# MOD-W_V03.net
KiCad netlist of a schematic drawn in EAGLE
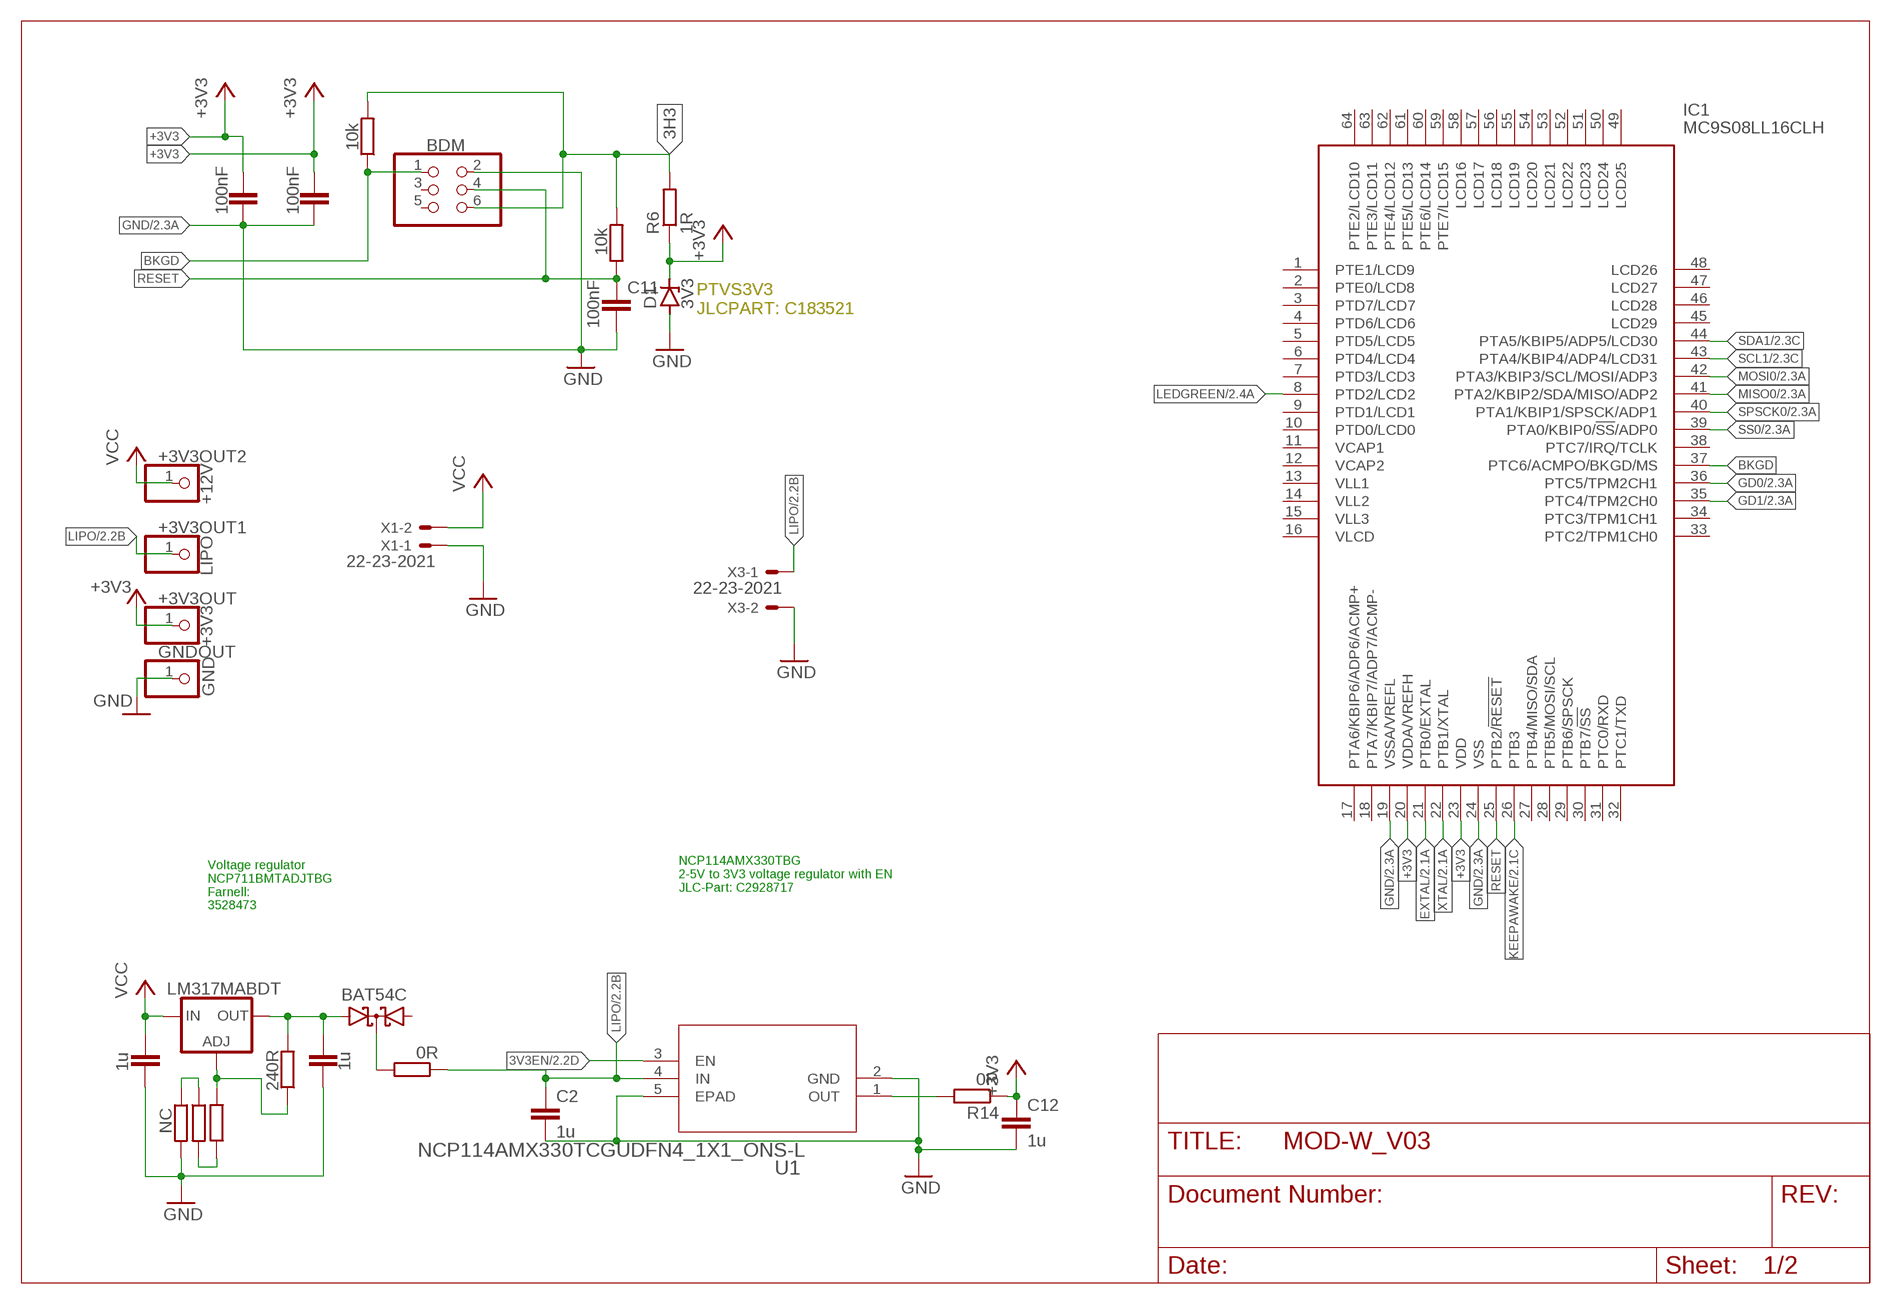
[diagram p0: schematic, sheet 1]
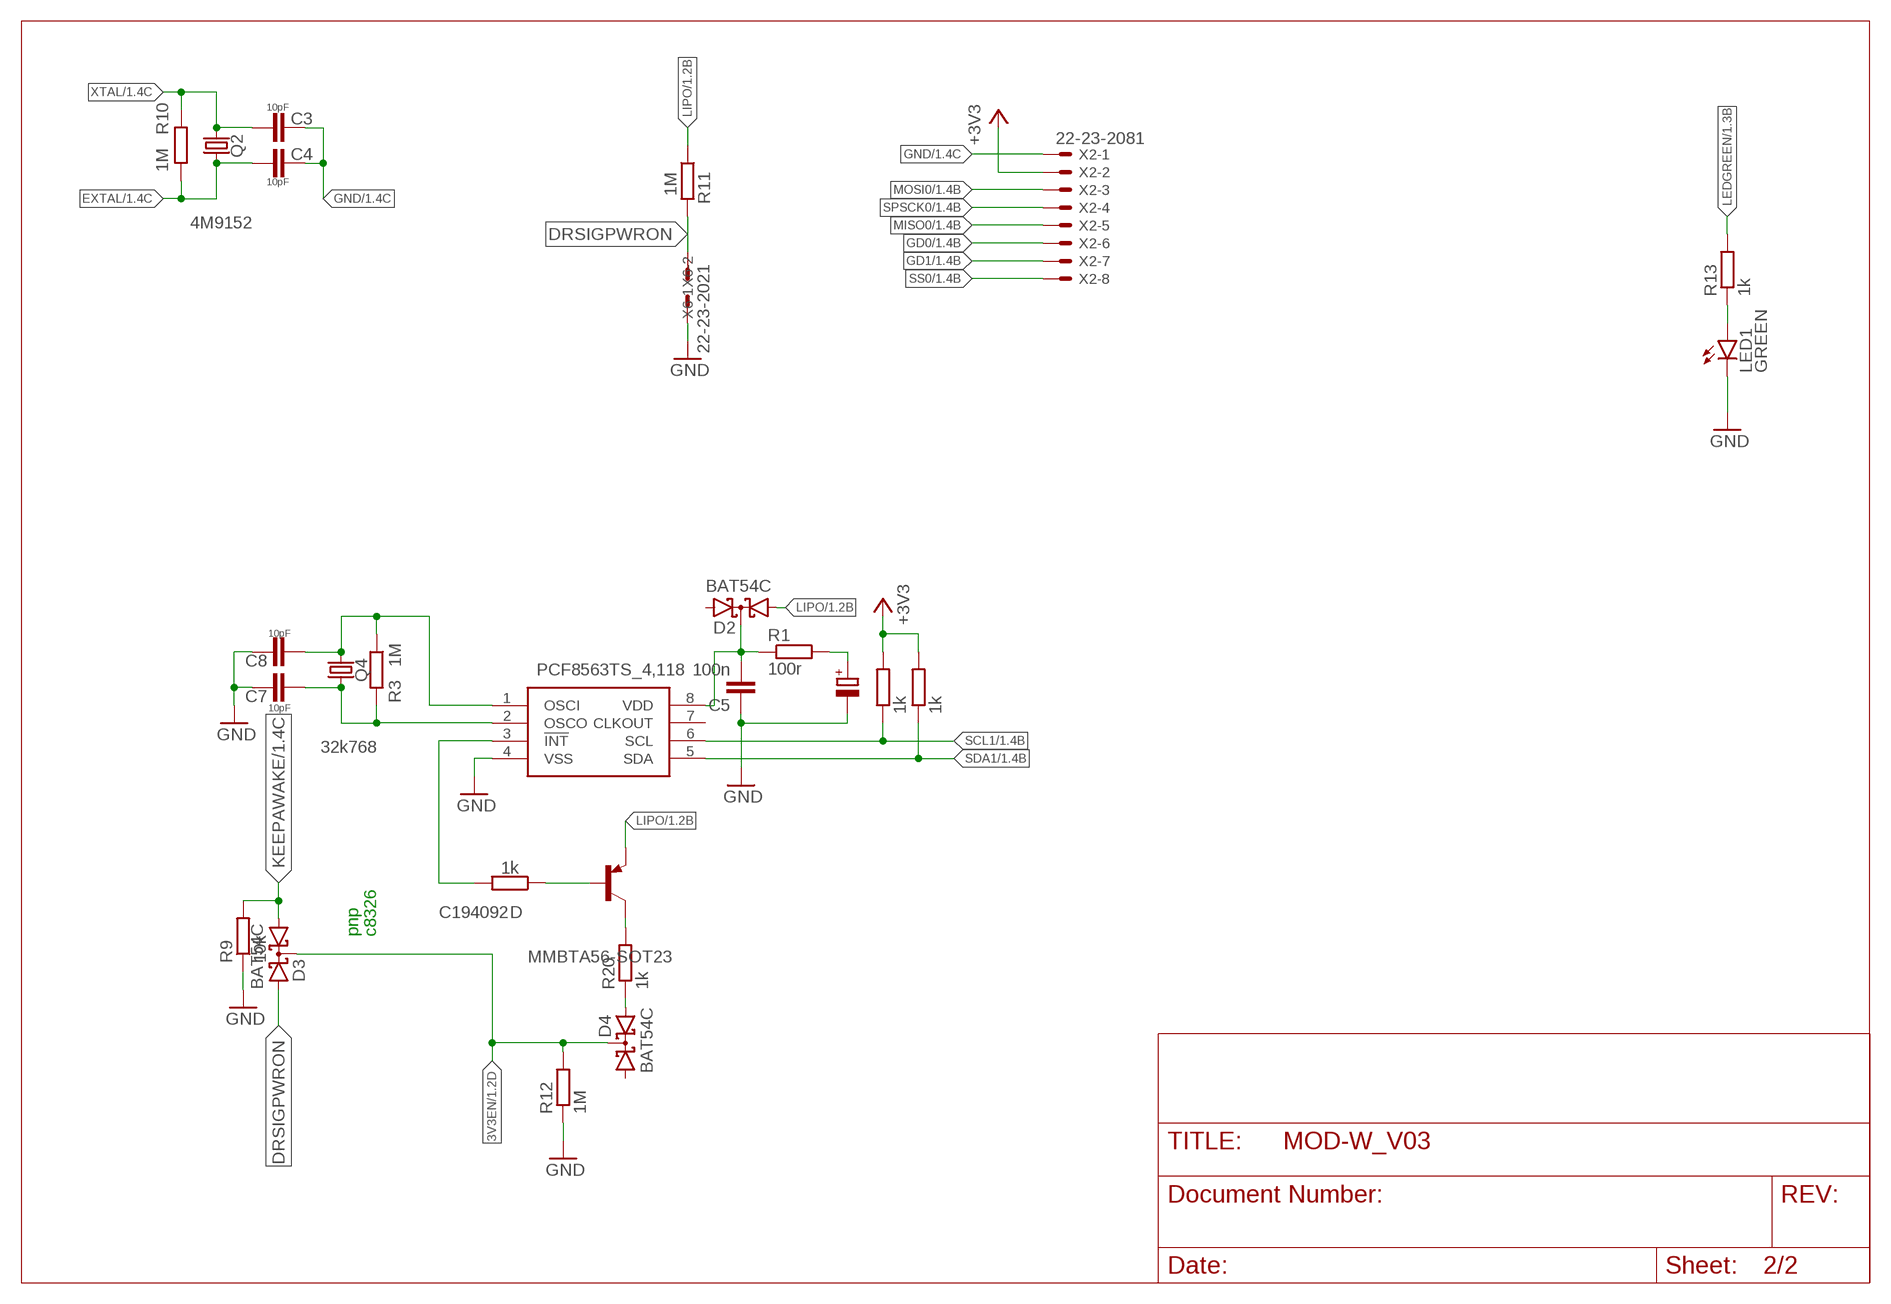
[diagram p1: schematic, sheet 2]

(export (version "E")
  (design (tool "Eeschema 10.0.6"))
  (components
    (comp (ref "+3V3OUT")
      (value "+3V3")
      (footprint "eagle-import:1X01")
      (libsource (lib "eagle-import") (part "PINHD-1X1"))
    )
    (comp (ref "+3V3OUT1")
      (value "LIPO")
      (footprint "eagle-import:1X01")
      (libsource (lib "eagle-import") (part "PINHD-1X1"))
    )
    (comp (ref "+3V3OUT2")
      (value "+12V")
      (footprint "eagle-import:1X01")
      (libsource (lib "eagle-import") (part "PINHD-1X1"))
    )
    (comp (ref "BDM")
      (value "PINHD-2X3")
      (footprint "eagle-import:2X03")
      (libsource (lib "eagle-import") (part "PINHD-2X3"))
    )
    (comp (ref "C1")
      (value "1u")
      (footprint "eagle-import:C0805")
      (libsource (lib "eagle-import") (part "C-EUC0805"))
    )
    (comp (ref "C2")
      (value "1u")
      (footprint "eagle-import:C0805")
      (libsource (lib "eagle-import") (part "C-EUC0805"))
    )
    (comp (ref "C9")
      (value "100nF")
      (footprint "eagle-import:C0805")
      (libsource (lib "eagle-import") (part "C-EUC0805"))
    )
    (comp (ref "C10")
      (value "100nF")
      (footprint "eagle-import:C0805")
      (libsource (lib "eagle-import") (part "C-EUC0805"))
    )
    (comp (ref "C11")
      (value "100nF")
      (footprint "eagle-import:C0805")
      (libsource (lib "eagle-import") (part "C-EUC0805"))
    )
    (comp (ref "C12")
      (value "1u")
      (footprint "eagle-import:C0805")
      (libsource (lib "eagle-import") (part "C-EUC0805"))
    )
    (comp (ref "C13")
      (value "1u")
      (footprint "eagle-import:C0805")
      (libsource (lib "eagle-import") (part "C-EUC0805"))
    )
    (comp (ref "D1")
      (value "3V3")
      (footprint "eagle-import:SOD80C")
      (libsource (lib "eagle-import") (part "ZENER-DIODESOD80C"))
    )
    (comp (ref "D7")
      (value "BAT54C")
      (footprint "eagle-import:SOT23")
      (libsource (lib "eagle-import") (part "BAT54C"))
    )
    (comp (ref "GNDOUT")
      (value "GND")
      (footprint "eagle-import:1X01")
      (libsource (lib "eagle-import") (part "PINHD-1X1"))
    )
    (comp (ref "IC1")
      (value "MC9S08LL16CLH")
      (footprint "eagle-import:QFP50P1200X1200X160-64N")
      (fields (field (name "MOUSER_PART_NUMBER") "841-MC9S08LL16CLH"))
      (libsource (lib "eagle-import") (part "MC9S08LL16CLH"))
    )
    (comp (ref "IC4")
      (value "LM317MABDT")
      (footprint "eagle-import:DPACK")
      (libsource (lib "eagle-import") (part "v-reg_409_LM317?MABDT"))
    )
    (comp (ref "R2")
      (value "NC")
      (footprint "eagle-import:R0805")
      (libsource (lib "eagle-import") (part "R-EU_R0805"))
    )
    (comp (ref "R6")
      (value "1R")
      (footprint "eagle-import:R0805")
      (libsource (lib "eagle-import") (part "R-EU_R0805"))
    )
    (comp (ref "R7")
      (value "0R")
      (footprint "eagle-import:R0805")
      (libsource (lib "eagle-import") (part "R-EU_R0805"))
    )
    (comp (ref "R14")
      (value "0R")
      (footprint "eagle-import:R0805")
      (libsource (lib "eagle-import") (part "R-EU_R0805"))
    )
    (comp (ref "R15")
      (value "240R")
      (footprint "eagle-import:R0805")
      (libsource (lib "eagle-import") (part "R-EU_R0805"))
    )
    (comp (ref "R16")
      (value "10k")
      (footprint "eagle-import:R0805")
      (libsource (lib "eagle-import") (part "R-EU_R0805"))
    )
    (comp (ref "R17")
      (value "10k")
      (footprint "eagle-import:R0805")
      (libsource (lib "eagle-import") (part "R-EU_R0805"))
    )
    (comp (ref "R18")
      (value "NC")
      (footprint "eagle-import:R0805")
      (libsource (lib "eagle-import") (part "R-EU_R0805"))
    )
    (comp (ref "R19")
      (value "NC")
      (footprint "eagle-import:R0805")
      (libsource (lib "eagle-import") (part "R-EU_R0805"))
    )
    (comp (ref "U1")
      (value "NCP114AMX330TCGUDFN4_1X1_ONS-L")
      (footprint "eagle-import:UDFN4_1X1_ONS-L")
      (fields
        (field (name "MANUFACTURER_PART_NUMBER") "NCP114AMX330TCG")
        (field (name "COPYRIGHT") "Copyright (C) 2022 Ultra Librarian. All rights reserved.")
      )
      (libsource (lib "eagle-import") (part "NCP114AMX330TCGUDFN4_1X1_ONS-L"))
    )
    (comp (ref "X1")
      (value "22-23-2021")
      (footprint "eagle-import:22-23-2021")
      (fields (field (name "MF") "MOLEX"))
      (libsource (lib "eagle-import") (part "22-23-2021"))
    )
    (comp (ref "X3")
      (value "22-23-2021")
      (footprint "eagle-import:22-23-2021")
      (fields (field (name "MF") "MOLEX"))
      (libsource (lib "eagle-import") (part "22-23-2021"))
    )
    (comp (ref "C3")
      (value "10pF")
      (footprint "eagle-import:C0805")
      (libsource (lib "eagle-import") (part "C-EUC0805"))
    )
    (comp (ref "C4")
      (value "10pF")
      (footprint "eagle-import:C0805")
      (libsource (lib "eagle-import") (part "C-EUC0805"))
    )
    (comp (ref "C5")
      (value "100n")
      (footprint "eagle-import:C0805")
      (libsource (lib "eagle-import") (part "C-EUC0805"))
    )
    (comp (ref "C6")
      (value "100u")
      (footprint "eagle-import:PANASONIC_E")
      (libsource (lib "eagle-import") (part "CPOL-EUE"))
    )
    (comp (ref "C7")
      (value "10pF")
      (footprint "eagle-import:C0805")
      (libsource (lib "eagle-import") (part "C-EUC0805"))
    )
    (comp (ref "C8")
      (value "10pF")
      (footprint "eagle-import:C0805")
      (libsource (lib "eagle-import") (part "C-EUC0805"))
    )
    (comp (ref "D2")
      (value "BAT54C")
      (footprint "eagle-import:SOT23")
      (libsource (lib "eagle-import") (part "BAT54C"))
    )
    (comp (ref "D3")
      (value "BAT54C")
      (footprint "eagle-import:SOT23")
      (libsource (lib "eagle-import") (part "BAT54C"))
    )
    (comp (ref "D4")
      (value "BAT54C")
      (footprint "eagle-import:SOT23")
      (libsource (lib "eagle-import") (part "BAT54C"))
    )
    (comp (ref "IC3")
      (value "PCF8563TS_4,118")
      (footprint "eagle-import:SOP65P490X110-8N")
      (fields
        (field (name "ARROW_PART_NUMBER") "PCF8563TS/4,118")
        (field (name "MOUSER_PART_NUMBER") "771-PCF8563TS-T")
      )
      (libsource (lib "eagle-import") (part "PCF8563TS_4,118"))
    )
    (comp (ref "LED1")
      (value "GREEN")
      (footprint "eagle-import:CHIP-LED0805")
      (libsource (lib "eagle-import") (part "LEDCHIP-LED0805"))
    )
    (comp (ref "Q2")
      (value "4M9152")
      (footprint "eagle-import:HC49UP")
      (libsource (lib "eagle-import") (part "CRYSTALHC49UP"))
    )
    (comp (ref "Q3")
      (value "MMBTA56-SOT23")
      (footprint "eagle-import:SOT23")
      (libsource (lib "eagle-import") (part "-?SOT23MMBTA56"))
    )
    (comp (ref "Q4")
      (value "32k768")
      (footprint "eagle-import:TC38H")
      (libsource (lib "eagle-import") (part "CRYSTALTC38H"))
    )
    (comp (ref "R1")
      (value "100r")
      (footprint "eagle-import:R0805")
      (libsource (lib "eagle-import") (part "R-EU_R0805"))
    )
    (comp (ref "R3")
      (value "1M")
      (footprint "eagle-import:R0805")
      (libsource (lib "eagle-import") (part "R-EU_R0805"))
    )
    (comp (ref "R4")
      (value "1k")
      (footprint "eagle-import:R0805")
      (libsource (lib "eagle-import") (part "R-EU_R0805"))
    )
    (comp (ref "R5")
      (value "1k")
      (footprint "eagle-import:R0805")
      (libsource (lib "eagle-import") (part "R-EU_R0805"))
    )
    (comp (ref "R8")
      (value "1k")
      (footprint "eagle-import:R0805")
      (libsource (lib "eagle-import") (part "R-EU_R0805"))
    )
    (comp (ref "R9")
      (value "10k")
      (footprint "eagle-import:R0805")
      (libsource (lib "eagle-import") (part "R-EU_R0805"))
    )
    (comp (ref "R10")
      (value "1M")
      (footprint "eagle-import:R0805")
      (libsource (lib "eagle-import") (part "R-EU_R0805"))
    )
    (comp (ref "R11")
      (value "1M")
      (footprint "eagle-import:R0805")
      (libsource (lib "eagle-import") (part "R-EU_R0805"))
    )
    (comp (ref "R12")
      (value "1M")
      (footprint "eagle-import:R0805")
      (libsource (lib "eagle-import") (part "R-EU_R0805"))
    )
    (comp (ref "R13")
      (value "1k")
      (footprint "eagle-import:R0805")
      (libsource (lib "eagle-import") (part "R-EU_R0805"))
    )
    (comp (ref "R20")
      (value "1k")
      (footprint "eagle-import:R0805")
      (libsource (lib "eagle-import") (part "R-EU_R0805"))
    )
    (comp (ref "X2")
      (value "22-23-2081")
      (footprint "eagle-import:22-23-2081")
      (fields (field (name "MF") "MOLEX"))
      (libsource (lib "eagle-import") (part "22-23-2081"))
    )
    (comp (ref "X6")
      (value "22-23-2021")
      (footprint "eagle-import:22-23-2021")
      (fields (field (name "MF") "MOLEX"))
      (libsource (lib "eagle-import") (part "22-23-2021"))
    )
  )
  (nets
    (net (code "1") (name "+3V3") (class "Default")
      (node (ref "+3V3OUT") (pin "1") (pinfunction "1_1") (pintype "passive"))
      (node (ref "C10") (pin "1") (pinfunction "1_1") (pintype "passive"))
      (node (ref "C12") (pin "1") (pinfunction "1_1") (pintype "passive"))
      (node (ref "C9") (pin "1") (pinfunction "1_1") (pintype "passive"))
      (node (ref "D1") (pin "C") (pinfunction "C_C") (pintype "passive"))
      (node (ref "IC1") (pin "20") (pinfunction "VDDA/VREFH_20") (pintype "bidirectional"))
      (node (ref "IC1") (pin "23") (pinfunction "VDD_23") (pintype "bidirectional"))
      (node (ref "R14") (pin "1") (pinfunction "1_1") (pintype "passive"))
      (node (ref "R4") (pin "2") (pinfunction "2_2") (pintype "passive"))
      (node (ref "R5") (pin "2") (pinfunction "2_2") (pintype "passive"))
      (node (ref "R6") (pin "1") (pinfunction "1_1") (pintype "passive"))
      (node (ref "X2") (pin "2") (pinfunction "S_2") (pintype "passive"))
    )
    (net (code "2") (name "3H3") (class "Default")
      (node (ref "BDM") (pin "6") (pinfunction "6_6") (pintype "passive"))
      (node (ref "R16") (pin "2") (pinfunction "2_2") (pintype "passive"))
      (node (ref "R17") (pin "2") (pinfunction "2_2") (pintype "passive"))
      (node (ref "R6") (pin "2") (pinfunction "2_2") (pintype "passive"))
    )
    (net (code "3") (name "3V3EN") (class "Default")
      (node (ref "D3") (pin "3") (pinfunction "CC_3") (pintype "passive"))
      (node (ref "D4") (pin "3") (pinfunction "CC_3") (pintype "passive"))
      (node (ref "R12") (pin "2") (pinfunction "2_2") (pintype "passive"))
      (node (ref "U1") (pin "3") (pinfunction "EN_3") (pintype "passive"))
    )
    (net (code "4") (name "BKGD") (class "Default")
      (node (ref "BDM") (pin "1") (pinfunction "1_1") (pintype "passive"))
      (node (ref "IC1") (pin "37") (pinfunction "PTC6/ACMPO/BKGD/MS_37") (pintype "bidirectional"))
      (node (ref "R16") (pin "1") (pinfunction "1_1") (pintype "passive"))
    )
    (net (code "5") (name "DRSIGPWRON") (class "Default")
      (node (ref "D3") (pin "2") (pinfunction "A2_2") (pintype "passive"))
      (node (ref "R11") (pin "2") (pinfunction "2_2") (pintype "passive"))
      (node (ref "X6") (pin "1") (pinfunction "S_1") (pintype "passive"))
    )
    (net (code "6") (name "EXTAL") (class "Default")
      (node (ref "C4") (pin "1") (pinfunction "1_1") (pintype "passive"))
      (node (ref "IC1") (pin "21") (pinfunction "PTB0/EXTAL_21") (pintype "bidirectional"))
      (node (ref "Q2") (pin "1") (pinfunction "1_1") (pintype "passive"))
      (node (ref "R10") (pin "1") (pinfunction "1_1") (pintype "passive"))
    )
    (net (code "7") (name "GD0") (class "Default")
      (node (ref "IC1") (pin "36") (pinfunction "PTC5/TPM2CH1_36") (pintype "bidirectional"))
      (node (ref "X2") (pin "6") (pinfunction "S_6") (pintype "passive"))
    )
    (net (code "8") (name "GD1") (class "Default")
      (node (ref "IC1") (pin "35") (pinfunction "PTC4/TPM2CH0_35") (pintype "bidirectional"))
      (node (ref "X2") (pin "7") (pinfunction "S_7") (pintype "passive"))
    )
    (net (code "9") (name "GND") (class "Default")
      (node (ref "BDM") (pin "2") (pinfunction "2_2") (pintype "passive"))
      (node (ref "C1") (pin "2") (pinfunction "2_2") (pintype "passive"))
      (node (ref "C10") (pin "2") (pinfunction "2_2") (pintype "passive"))
      (node (ref "C11") (pin "2") (pinfunction "2_2") (pintype "passive"))
      (node (ref "C12") (pin "2") (pinfunction "2_2") (pintype "passive"))
      (node (ref "C13") (pin "2") (pinfunction "2_2") (pintype "passive"))
      (node (ref "C2") (pin "2") (pinfunction "2_2") (pintype "passive"))
      (node (ref "C3") (pin "2") (pinfunction "2_2") (pintype "passive"))
      (node (ref "C4") (pin "2") (pinfunction "2_2") (pintype "passive"))
      (node (ref "C5") (pin "1") (pinfunction "1_1") (pintype "passive"))
      (node (ref "C6") (pin "-") (pinfunction "-_-") (pintype "passive"))
      (node (ref "C7") (pin "2") (pinfunction "2_2") (pintype "passive"))
      (node (ref "C8") (pin "2") (pinfunction "2_2") (pintype "passive"))
      (node (ref "C9") (pin "2") (pinfunction "2_2") (pintype "passive"))
      (node (ref "D1") (pin "A") (pinfunction "A_A") (pintype "passive"))
      (node (ref "GNDOUT") (pin "1") (pinfunction "1_1") (pintype "passive"))
      (node (ref "IC1") (pin "19") (pinfunction "VSSA/VREFL_19") (pintype "bidirectional"))
      (node (ref "IC1") (pin "24") (pinfunction "VSS_24") (pintype "bidirectional"))
      (node (ref "IC3") (pin "4") (pinfunction "VSS_4") (pintype "bidirectional"))
      (node (ref "LED1") (pin "C") (pinfunction "C_C") (pintype "passive"))
      (node (ref "R12") (pin "1") (pinfunction "1_1") (pintype "passive"))
      (node (ref "R19") (pin "2") (pinfunction "2_2") (pintype "passive"))
      (node (ref "R9") (pin "1") (pinfunction "1_1") (pintype "passive"))
      (node (ref "U1") (pin "2") (pinfunction "GND_2") (pintype "power_in"))
      (node (ref "U1") (pin "5") (pinfunction "EPAD_5") (pintype "passive"))
      (node (ref "X1") (pin "1") (pinfunction "S_1") (pintype "passive"))
      (node (ref "X2") (pin "1") (pinfunction "S_1") (pintype "passive"))
      (node (ref "X3") (pin "2") (pinfunction "S_2") (pintype "passive"))
      (node (ref "X6") (pin "2") (pinfunction "S_2") (pintype "passive"))
    )
    (net (code "10") (name "KEEPAWAKE") (class "Default")
      (node (ref "D3") (pin "1") (pinfunction "A1_1") (pintype "passive"))
      (node (ref "IC1") (pin "26") (pinfunction "PTB3_26") (pintype "bidirectional"))
      (node (ref "R9") (pin "2") (pinfunction "2_2") (pintype "passive"))
    )
    (net (code "11") (name "LEDGREEN") (class "Default")
      (node (ref "IC1") (pin "8") (pinfunction "PTD2/LCD2_8") (pintype "bidirectional"))
      (node (ref "R13") (pin "2") (pinfunction "2_2") (pintype "passive"))
    )
    (net (code "12") (name "LIPO") (class "Default")
      (node (ref "+3V3OUT1") (pin "1") (pinfunction "1_1") (pintype "passive"))
      (node (ref "C2") (pin "1") (pinfunction "1_1") (pintype "passive"))
      (node (ref "D2") (pin "1") (pinfunction "A1_1") (pintype "passive"))
      (node (ref "Q3") (pin "2") (pinfunction "E_2") (pintype "passive"))
      (node (ref "R11") (pin "1") (pinfunction "1_1") (pintype "passive"))
      (node (ref "R7") (pin "1") (pinfunction "1_1") (pintype "passive"))
      (node (ref "U1") (pin "4") (pinfunction "IN_4") (pintype "input"))
      (node (ref "X3") (pin "1") (pinfunction "S_1") (pintype "passive"))
    )
    (net (code "13") (name "MISO0") (class "Default")
      (node (ref "IC1") (pin "41") (pinfunction "PTA2/KBIP2/SDA/MISO/ADP2_41") (pintype "bidirectional"))
      (node (ref "X2") (pin "5") (pinfunction "S_5") (pintype "passive"))
    )
    (net (code "14") (name "MOSI0") (class "Default")
      (node (ref "IC1") (pin "42") (pinfunction "PTA3/KBIP3/SCL/MOSI/ADP3_42") (pintype "bidirectional"))
      (node (ref "X2") (pin "3") (pinfunction "S_3") (pintype "passive"))
    )
    (net (code "15") (name "Net-(C6-Pad+)") (class "Default")
      (node (ref "C6") (pin "+") (pinfunction "+_+") (pintype "passive"))
      (node (ref "R1") (pin "2") (pinfunction "2_2") (pintype "passive"))
    )
    (net (code "16") (name "Net-(D2-CC)") (class "Default")
      (node (ref "C5") (pin "2") (pinfunction "2_2") (pintype "passive"))
      (node (ref "D2") (pin "3") (pinfunction "CC_3") (pintype "passive"))
      (node (ref "IC3") (pin "8") (pinfunction "VDD_8") (pintype "bidirectional"))
      (node (ref "R1") (pin "1") (pinfunction "1_1") (pintype "passive"))
    )
    (net (code "17") (name "Net-(D4-A2)") (class "Default")
      (node (ref "D4") (pin "2") (pinfunction "A2_2") (pintype "passive"))
      (node (ref "R20") (pin "1") (pinfunction "1_1") (pintype "passive"))
    )
    (net (code "18") (name "Net-(D7-A2)") (class "Default")
      (node (ref "C1") (pin "1") (pinfunction "1_1") (pintype "passive"))
      (node (ref "D7") (pin "2") (pinfunction "A2_2") (pintype "passive"))
      (node (ref "IC4") (pin "4") (pinfunction "OUT_4") (pintype "passive"))
      (node (ref "R15") (pin "2") (pinfunction "2_2") (pintype "passive"))
    )
    (net (code "19") (name "Net-(D7-CC)") (class "Default")
      (node (ref "D7") (pin "3") (pinfunction "CC_3") (pintype "passive"))
      (node (ref "R7") (pin "2") (pinfunction "2_2") (pintype "passive"))
    )
    (net (code "20") (name "Net-(IC3-OSCI)") (class "Default")
      (node (ref "C8") (pin "1") (pinfunction "1_1") (pintype "passive"))
      (node (ref "IC3") (pin "1") (pinfunction "OSCI_1") (pintype "bidirectional"))
      (node (ref "Q4") (pin "2") (pinfunction "2_2") (pintype "passive"))
      (node (ref "R3") (pin "1") (pinfunction "1_1") (pintype "passive"))
    )
    (net (code "21") (name "Net-(IC3-OSCO)") (class "Default")
      (node (ref "C7") (pin "1") (pinfunction "1_1") (pintype "passive"))
      (node (ref "IC3") (pin "2") (pinfunction "OSCO_2") (pintype "bidirectional"))
      (node (ref "Q4") (pin "1") (pinfunction "1_1") (pintype "passive"))
      (node (ref "R3") (pin "2") (pinfunction "2_2") (pintype "passive"))
    )
    (net (code "22") (name "Net-(IC3-~{INT})") (class "Default")
      (node (ref "IC3") (pin "3") (pinfunction "~{INT}_3") (pintype "bidirectional"))
      (node (ref "R8") (pin "2") (pinfunction "2_2") (pintype "passive"))
    )
    (net (code "23") (name "Net-(IC4-ADJ)") (class "Default")
      (node (ref "IC4") (pin "1") (pinfunction "ADJ_1") (pintype "input"))
      (node (ref "R15") (pin "1") (pinfunction "1_1") (pintype "passive"))
      (node (ref "R18") (pin "2") (pinfunction "2_2") (pintype "passive"))
    )
    (net (code "24") (name "Net-(LED1-PadA)") (class "Default")
      (node (ref "LED1") (pin "A") (pinfunction "A_A") (pintype "passive"))
      (node (ref "R13") (pin "1") (pinfunction "1_1") (pintype "passive"))
    )
    (net (code "25") (name "Net-(Q3-B)") (class "Default")
      (node (ref "Q3") (pin "1") (pinfunction "B_1") (pintype "passive"))
      (node (ref "R8") (pin "1") (pinfunction "1_1") (pintype "passive"))
    )
    (net (code "26") (name "Net-(Q3-C)") (class "Default")
      (node (ref "Q3") (pin "3") (pinfunction "C_3") (pintype "passive"))
      (node (ref "R20") (pin "2") (pinfunction "2_2") (pintype "passive"))
    )
    (net (code "27") (name "Net-(R18-Pad1)") (class "Default")
      (node (ref "R18") (pin "1") (pinfunction "1_1") (pintype "passive"))
      (node (ref "R2") (pin "2") (pinfunction "2_2") (pintype "passive"))
    )
    (net (code "28") (name "Net-(R19-Pad1)") (class "Default")
      (node (ref "R19") (pin "1") (pinfunction "1_1") (pintype "passive"))
      (node (ref "R2") (pin "1") (pinfunction "1_1") (pintype "passive"))
    )
    (net (code "29") (name "Net-(U1-OUT)") (class "Default")
      (node (ref "R14") (pin "2") (pinfunction "2_2") (pintype "passive"))
      (node (ref "U1") (pin "1") (pinfunction "OUT_1") (pintype "output"))
    )
    (net (code "30") (name "RESET") (class "Default")
      (node (ref "BDM") (pin "4") (pinfunction "4_4") (pintype "passive"))
      (node (ref "C11") (pin "1") (pinfunction "1_1") (pintype "passive"))
      (node (ref "IC1") (pin "25") (pinfunction "PTB2/~{RESET}_25") (pintype "bidirectional"))
      (node (ref "R17") (pin "1") (pinfunction "1_1") (pintype "passive"))
    )
    (net (code "31") (name "SCL1") (class "Default")
      (node (ref "IC1") (pin "43") (pinfunction "PTA4/KBIP4/ADP4/LCD31_43") (pintype "bidirectional"))
      (node (ref "IC3") (pin "6") (pinfunction "SCL_6") (pintype "bidirectional"))
      (node (ref "R4") (pin "1") (pinfunction "1_1") (pintype "passive"))
    )
    (net (code "32") (name "SDA1") (class "Default")
      (node (ref "IC1") (pin "44") (pinfunction "PTA5/KBIP5/ADP5/LCD30_44") (pintype "bidirectional"))
      (node (ref "IC3") (pin "5") (pinfunction "SDA_5") (pintype "bidirectional"))
      (node (ref "R5") (pin "1") (pinfunction "1_1") (pintype "passive"))
    )
    (net (code "33") (name "SPSCK0") (class "Default")
      (node (ref "IC1") (pin "40") (pinfunction "PTA1/KBIP1/SPSCK/ADP1_40") (pintype "bidirectional"))
      (node (ref "X2") (pin "4") (pinfunction "S_4") (pintype "passive"))
    )
    (net (code "34") (name "SS0") (class "Default")
      (node (ref "IC1") (pin "39") (pinfunction "PTA0/KBIP0/~{SS}/ADP0_39") (pintype "bidirectional"))
      (node (ref "X2") (pin "8") (pinfunction "S_8") (pintype "passive"))
    )
    (net (code "35") (name "VCC") (class "Default")
      (node (ref "+3V3OUT2") (pin "1") (pinfunction "1_1") (pintype "passive"))
      (node (ref "C13") (pin "1") (pinfunction "1_1") (pintype "passive"))
      (node (ref "IC4") (pin "3") (pinfunction "IN_3") (pintype "input"))
      (node (ref "X1") (pin "2") (pinfunction "S_2") (pintype "passive"))
    )
    (net (code "36") (name "XTAL") (class "Default")
      (node (ref "C3") (pin "1") (pinfunction "1_1") (pintype "passive"))
      (node (ref "IC1") (pin "22") (pinfunction "PTB1/XTAL_22") (pintype "bidirectional"))
      (node (ref "Q2") (pin "2") (pinfunction "2_2") (pintype "passive"))
      (node (ref "R10") (pin "2") (pinfunction "2_2") (pintype "passive"))
    )
    (net (code "37") (name "unconnected-(BDM-Pad3)") (class "Default")
      (node (ref "BDM") (pin "3") (pinfunction "3_3") (pintype "passive"))
    )
    (net (code "38") (name "unconnected-(BDM-Pad5)") (class "Default")
      (node (ref "BDM") (pin "5") (pinfunction "5_5") (pintype "passive"))
    )
    (net (code "39") (name "unconnected-(D2-A2-Pad2)") (class "Default")
      (node (ref "D2") (pin "2") (pinfunction "A2_2") (pintype "passive"))
    )
    (net (code "40") (name "unconnected-(D4-A1-Pad1)") (class "Default")
      (node (ref "D4") (pin "1") (pinfunction "A1_1") (pintype "passive"))
    )
    (net (code "41") (name "unconnected-(D7-A1-Pad1)") (class "Default")
      (node (ref "D7") (pin "1") (pinfunction "A1_1") (pintype "passive"))
    )
    (net (code "42") (name "unconnected-(IC1-LCD16-Pad58)") (class "Default")
      (node (ref "IC1") (pin "58") (pinfunction "LCD16_58") (pintype "bidirectional"))
    )
    (net (code "43") (name "unconnected-(IC1-LCD17-Pad57)") (class "Default")
      (node (ref "IC1") (pin "57") (pinfunction "LCD17_57") (pintype "bidirectional"))
    )
    (net (code "44") (name "unconnected-(IC1-LCD18-Pad56)") (class "Default")
      (node (ref "IC1") (pin "56") (pinfunction "LCD18_56") (pintype "bidirectional"))
    )
    (net (code "45") (name "unconnected-(IC1-LCD19-Pad55)") (class "Default")
      (node (ref "IC1") (pin "55") (pinfunction "LCD19_55") (pintype "bidirectional"))
    )
    (net (code "46") (name "unconnected-(IC1-LCD20-Pad54)") (class "Default")
      (node (ref "IC1") (pin "54") (pinfunction "LCD20_54") (pintype "bidirectional"))
    )
    (net (code "47") (name "unconnected-(IC1-LCD21-Pad53)") (class "Default")
      (node (ref "IC1") (pin "53") (pinfunction "LCD21_53") (pintype "bidirectional"))
    )
    (net (code "48") (name "unconnected-(IC1-LCD22-Pad52)") (class "Default")
      (node (ref "IC1") (pin "52") (pinfunction "LCD22_52") (pintype "bidirectional"))
    )
    (net (code "49") (name "unconnected-(IC1-LCD23-Pad51)") (class "Default")
      (node (ref "IC1") (pin "51") (pinfunction "LCD23_51") (pintype "bidirectional"))
    )
    (net (code "50") (name "unconnected-(IC1-LCD24-Pad50)") (class "Default")
      (node (ref "IC1") (pin "50") (pinfunction "LCD24_50") (pintype "bidirectional"))
    )
    (net (code "51") (name "unconnected-(IC1-LCD25-Pad49)") (class "Default")
      (node (ref "IC1") (pin "49") (pinfunction "LCD25_49") (pintype "bidirectional"))
    )
    (net (code "52") (name "unconnected-(IC1-LCD26-Pad48)") (class "Default")
      (node (ref "IC1") (pin "48") (pinfunction "LCD26_48") (pintype "bidirectional"))
    )
    (net (code "53") (name "unconnected-(IC1-LCD27-Pad47)") (class "Default")
      (node (ref "IC1") (pin "47") (pinfunction "LCD27_47") (pintype "bidirectional"))
    )
    (net (code "54") (name "unconnected-(IC1-LCD28-Pad46)") (class "Default")
      (node (ref "IC1") (pin "46") (pinfunction "LCD28_46") (pintype "bidirectional"))
    )
    (net (code "55") (name "unconnected-(IC1-LCD29-Pad45)") (class "Default")
      (node (ref "IC1") (pin "45") (pinfunction "LCD29_45") (pintype "bidirectional"))
    )
    (net (code "56") (name "unconnected-(IC1-PTA6{slash}KBIP6{slash}ADP6{slash}ACMP+-Pad17)") (class "Default")
      (node (ref "IC1") (pin "17") (pinfunction "PTA6/KBIP6/ADP6/ACMP+_17") (pintype "bidirectional"))
    )
    (net (code "57") (name "unconnected-(IC1-PTA7{slash}KBIP7{slash}ADP7{slash}ACMP--Pad18)") (class "Default")
      (node (ref "IC1") (pin "18") (pinfunction "PTA7/KBIP7/ADP7/ACMP-_18") (pintype "bidirectional"))
    )
    (net (code "58") (name "unconnected-(IC1-PTB4{slash}MISO{slash}SDA-Pad27)") (class "Default")
      (node (ref "IC1") (pin "27") (pinfunction "PTB4/MISO/SDA_27") (pintype "bidirectional"))
    )
    (net (code "59") (name "unconnected-(IC1-PTB5{slash}MOSI{slash}SCL-Pad28)") (class "Default")
      (node (ref "IC1") (pin "28") (pinfunction "PTB5/MOSI/SCL_28") (pintype "bidirectional"))
    )
    (net (code "60") (name "unconnected-(IC1-PTB6{slash}SPSCK-Pad29)") (class "Default")
      (node (ref "IC1") (pin "29") (pinfunction "PTB6/SPSCK_29") (pintype "bidirectional"))
    )
    (net (code "61") (name "unconnected-(IC1-PTB7{slash}~{SS}-Pad30)") (class "Default")
      (node (ref "IC1") (pin "30") (pinfunction "PTB7/~{SS}_30") (pintype "bidirectional"))
    )
    (net (code "62") (name "unconnected-(IC1-PTC0{slash}RXD-Pad31)") (class "Default")
      (node (ref "IC1") (pin "31") (pinfunction "PTC0/RXD_31") (pintype "bidirectional"))
    )
    (net (code "63") (name "unconnected-(IC1-PTC1{slash}TXD-Pad32)") (class "Default")
      (node (ref "IC1") (pin "32") (pinfunction "PTC1/TXD_32") (pintype "bidirectional"))
    )
    (net (code "64") (name "unconnected-(IC1-PTC2{slash}TPM1CH0-Pad33)") (class "Default")
      (node (ref "IC1") (pin "33") (pinfunction "PTC2/TPM1CH0_33") (pintype "bidirectional"))
    )
    (net (code "65") (name "unconnected-(IC1-PTC3{slash}TPM1CH1-Pad34)") (class "Default")
      (node (ref "IC1") (pin "34") (pinfunction "PTC3/TPM1CH1_34") (pintype "bidirectional"))
    )
    (net (code "66") (name "unconnected-(IC1-PTC7{slash}IRQ{slash}TCLK-Pad38)") (class "Default")
      (node (ref "IC1") (pin "38") (pinfunction "PTC7/IRQ/TCLK_38") (pintype "bidirectional"))
    )
    (net (code "67") (name "unconnected-(IC1-PTD0{slash}LCD0-Pad10)") (class "Default")
      (node (ref "IC1") (pin "10") (pinfunction "PTD0/LCD0_10") (pintype "bidirectional"))
    )
    (net (code "68") (name "unconnected-(IC1-PTD1{slash}LCD1-Pad9)") (class "Default")
      (node (ref "IC1") (pin "9") (pinfunction "PTD1/LCD1_9") (pintype "bidirectional"))
    )
    (net (code "69") (name "unconnected-(IC1-PTD3{slash}LCD3-Pad7)") (class "Default")
      (node (ref "IC1") (pin "7") (pinfunction "PTD3/LCD3_7") (pintype "bidirectional"))
    )
    (net (code "70") (name "unconnected-(IC1-PTD4{slash}LCD4-Pad6)") (class "Default")
      (node (ref "IC1") (pin "6") (pinfunction "PTD4/LCD4_6") (pintype "bidirectional"))
    )
    (net (code "71") (name "unconnected-(IC1-PTD5{slash}LCD5-Pad5)") (class "Default")
      (node (ref "IC1") (pin "5") (pinfunction "PTD5/LCD5_5") (pintype "bidirectional"))
    )
    (net (code "72") (name "unconnected-(IC1-PTD6{slash}LCD6-Pad4)") (class "Default")
      (node (ref "IC1") (pin "4") (pinfunction "PTD6/LCD6_4") (pintype "bidirectional"))
    )
    (net (code "73") (name "unconnected-(IC1-PTD7{slash}LCD7-Pad3)") (class "Default")
      (node (ref "IC1") (pin "3") (pinfunction "PTD7/LCD7_3") (pintype "bidirectional"))
    )
    (net (code "74") (name "unconnected-(IC1-PTE0{slash}LCD8-Pad2)") (class "Default")
      (node (ref "IC1") (pin "2") (pinfunction "PTE0/LCD8_2") (pintype "bidirectional"))
    )
    (net (code "75") (name "unconnected-(IC1-PTE1{slash}LCD9-Pad1)") (class "Default")
      (node (ref "IC1") (pin "1") (pinfunction "PTE1/LCD9_1") (pintype "bidirectional"))
    )
    (net (code "76") (name "unconnected-(IC1-PTE2{slash}LCD10-Pad64)") (class "Default")
      (node (ref "IC1") (pin "64") (pinfunction "PTE2/LCD10_64") (pintype "bidirectional"))
    )
    (net (code "77") (name "unconnected-(IC1-PTE3{slash}LCD11-Pad63)") (class "Default")
      (node (ref "IC1") (pin "63") (pinfunction "PTE3/LCD11_63") (pintype "bidirectional"))
    )
    (net (code "78") (name "unconnected-(IC1-PTE4{slash}LCD12-Pad62)") (class "Default")
      (node (ref "IC1") (pin "62") (pinfunction "PTE4/LCD12_62") (pintype "bidirectional"))
    )
    (net (code "79") (name "unconnected-(IC1-PTE5{slash}LCD13-Pad61)") (class "Default")
      (node (ref "IC1") (pin "61") (pinfunction "PTE5/LCD13_61") (pintype "bidirectional"))
    )
    (net (code "80") (name "unconnected-(IC1-PTE6{slash}LCD14-Pad60)") (class "Default")
      (node (ref "IC1") (pin "60") (pinfunction "PTE6/LCD14_60") (pintype "bidirectional"))
    )
    (net (code "81") (name "unconnected-(IC1-PTE7{slash}LCD15-Pad59)") (class "Default")
      (node (ref "IC1") (pin "59") (pinfunction "PTE7/LCD15_59") (pintype "bidirectional"))
    )
    (net (code "82") (name "unconnected-(IC1-VCAP1-Pad11)") (class "Default")
      (node (ref "IC1") (pin "11") (pinfunction "VCAP1_11") (pintype "bidirectional"))
    )
    (net (code "83") (name "unconnected-(IC1-VCAP2-Pad12)") (class "Default")
      (node (ref "IC1") (pin "12") (pinfunction "VCAP2_12") (pintype "bidirectional"))
    )
    (net (code "84") (name "unconnected-(IC1-VLCD-Pad16)") (class "Default")
      (node (ref "IC1") (pin "16") (pinfunction "VLCD_16") (pintype "bidirectional"))
    )
    (net (code "85") (name "unconnected-(IC1-VLL1-Pad13)") (class "Default")
      (node (ref "IC1") (pin "13") (pinfunction "VLL1_13") (pintype "bidirectional"))
    )
    (net (code "86") (name "unconnected-(IC1-VLL2-Pad14)") (class "Default")
      (node (ref "IC1") (pin "14") (pinfunction "VLL2_14") (pintype "bidirectional"))
    )
    (net (code "87") (name "unconnected-(IC1-VLL3-Pad15)") (class "Default")
      (node (ref "IC1") (pin "15") (pinfunction "VLL3_15") (pintype "bidirectional"))
    )
    (net (code "88") (name "unconnected-(IC3-CLKOUT-Pad7)") (class "Default")
      (node (ref "IC3") (pin "7") (pinfunction "CLKOUT_7") (pintype "bidirectional"))
    )
  )
)
